# PIC_WIFI_DEV.net
KiCad netlist of a schematic drawn in EAGLE
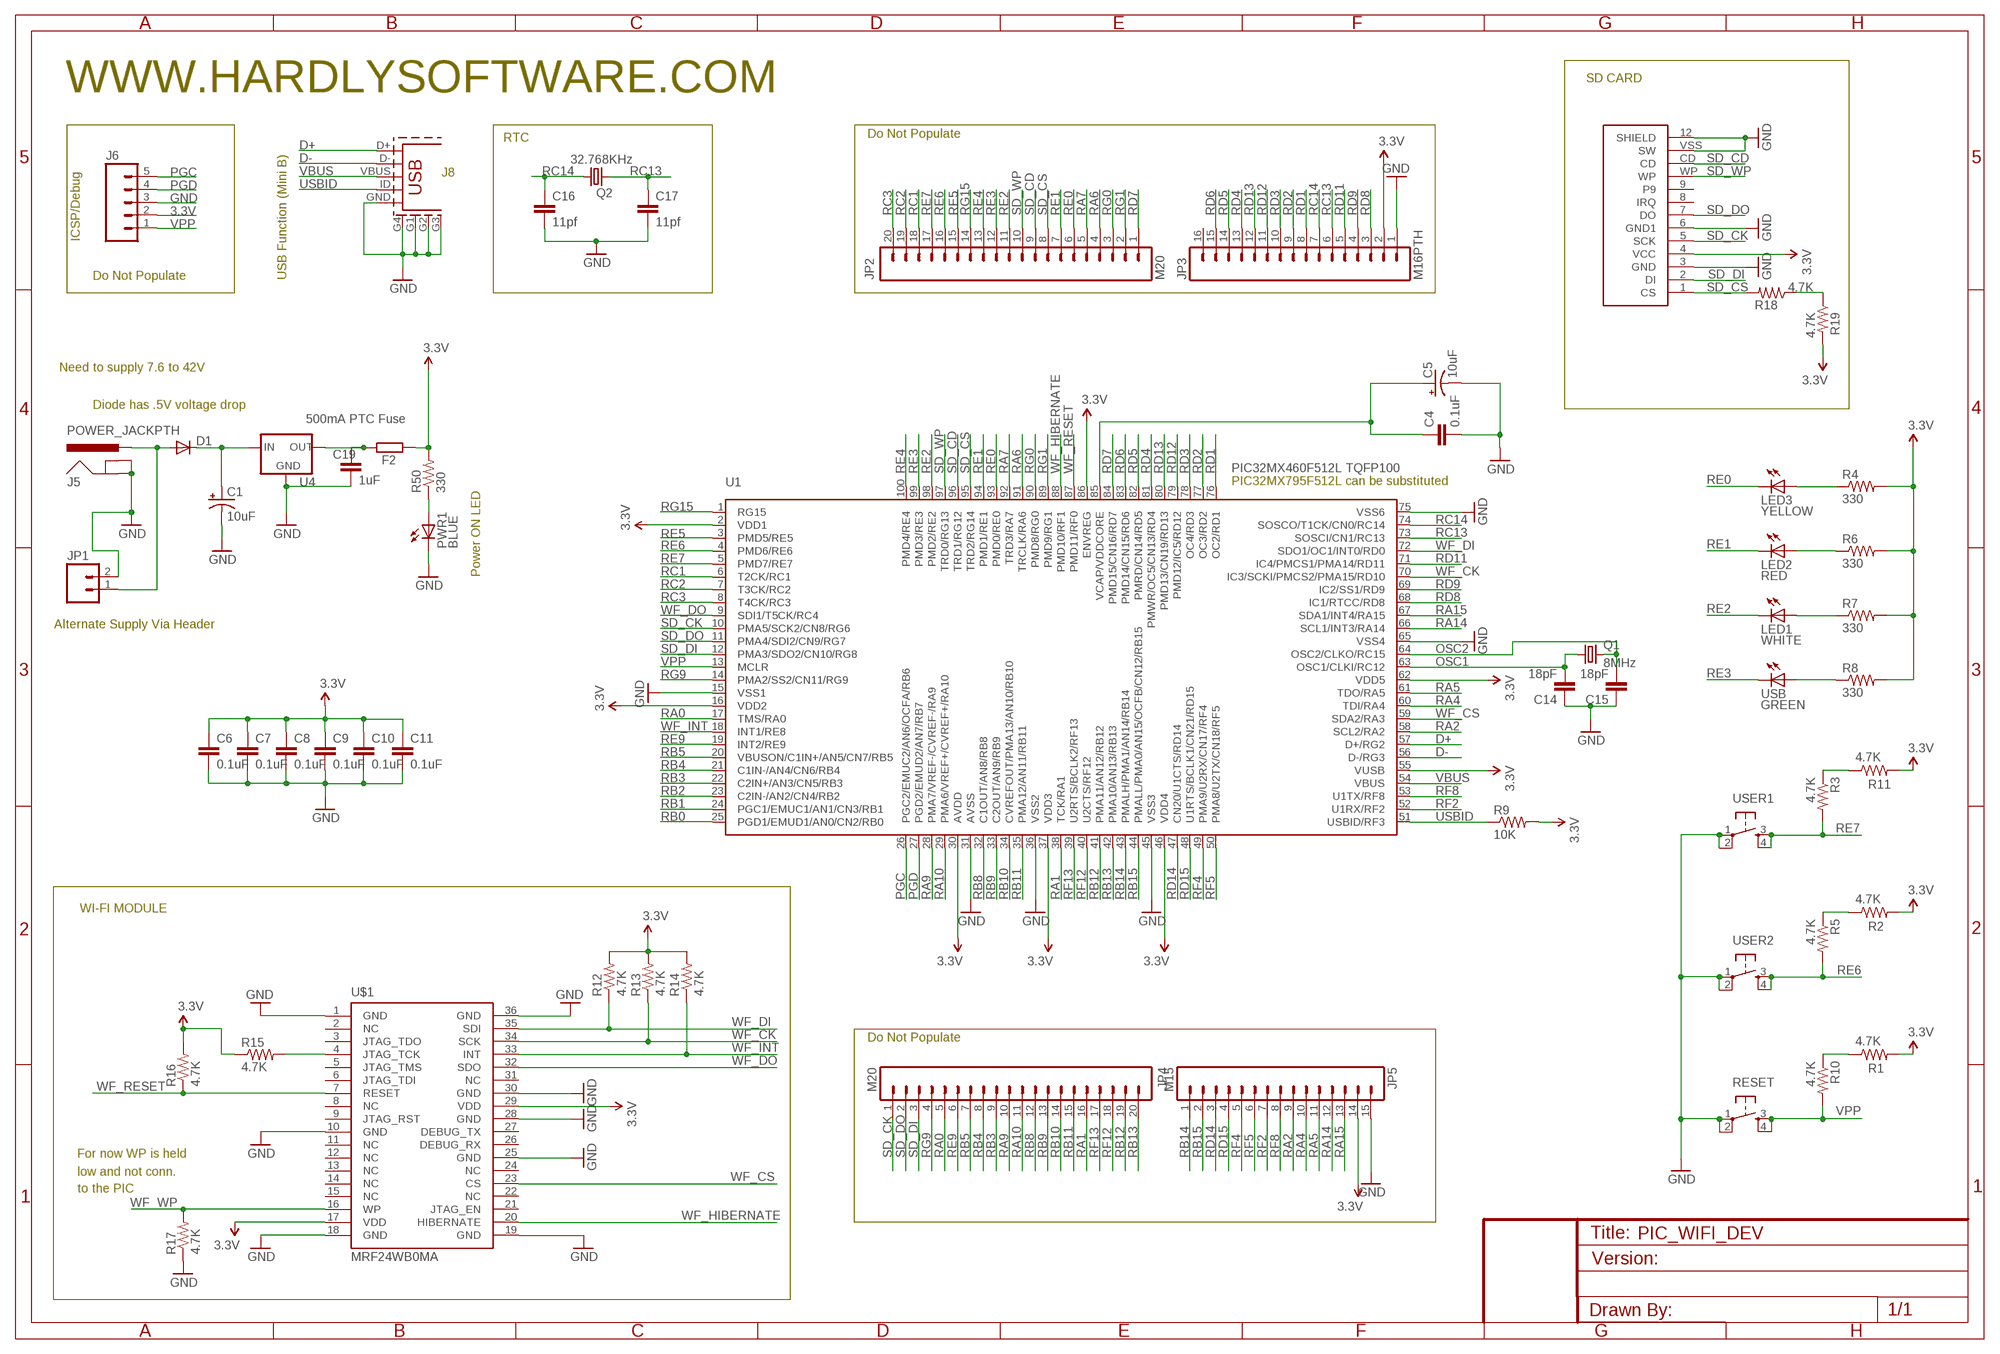
[diagram p0: schematic, sheet 1]

(export (version "E")
  (design (tool "Eeschema 10.0.6"))
  (components
    (comp (ref "C1")
      (value "10uF")
      (footprint "eagle-import:EIA3528")
      (libsource (lib "eagle-import") (part "CAP_POL3528"))
    )
    (comp (ref "C4")
      (value "0.1uF")
      (footprint "eagle-import:C0402")
      (libsource (lib "eagle-import") (part "CAP0402"))
    )
    (comp (ref "C5")
      (value "10uF")
      (footprint "eagle-import:EIA3528")
      (libsource (lib "eagle-import") (part "CAP_POL3528"))
    )
    (comp (ref "C6")
      (value "0.1uF")
      (footprint "eagle-import:C0402")
      (libsource (lib "eagle-import") (part "CAP0402"))
    )
    (comp (ref "C7")
      (value "0.1uF")
      (footprint "eagle-import:C0402")
      (libsource (lib "eagle-import") (part "CAP0402"))
    )
    (comp (ref "C8")
      (value "0.1uF")
      (footprint "eagle-import:C0402")
      (libsource (lib "eagle-import") (part "CAP0402"))
    )
    (comp (ref "C9")
      (value "0.1uF")
      (footprint "eagle-import:C0402")
      (libsource (lib "eagle-import") (part "CAP0402"))
    )
    (comp (ref "C10")
      (value "0.1uF")
      (footprint "eagle-import:C0402")
      (libsource (lib "eagle-import") (part "SparkFun02-20-08_CAP0402"))
    )
    (comp (ref "C11")
      (value "0.1uF")
      (footprint "eagle-import:C0402")
      (libsource (lib "eagle-import") (part "CAP0402"))
    )
    (comp (ref "C14")
      (value "18pF")
      (footprint "eagle-import:C0402")
      (libsource (lib "eagle-import") (part "CAP0402"))
    )
    (comp (ref "C15")
      (value "18pF")
      (footprint "eagle-import:C0402")
      (libsource (lib "eagle-import") (part "CAP0402"))
    )
    (comp (ref "C16")
      (value "11pf")
      (footprint "eagle-import:C0402")
      (libsource (lib "eagle-import") (part "CAP0402"))
    )
    (comp (ref "C17")
      (value "11pf")
      (footprint "eagle-import:C0402")
      (libsource (lib "eagle-import") (part "CAP0402"))
    )
    (comp (ref "C19")
      (value "1uF")
      (footprint "eagle-import:0603-CAP")
      (libsource (lib "eagle-import") (part "CAP0603-CAP"))
    )
    (comp (ref "D1")
      (value "DIODESMA")
      (footprint "eagle-import:SMA-DIODE")
      (libsource (lib "eagle-import") (part "DIODESMA"))
    )
    (comp (ref "F2")
      (value "500mA PTC Fuse")
      (footprint "eagle-import:M1206")
      (libsource (lib "eagle-import") (part "R-EU_M1206"))
    )
    (comp (ref "J5")
      (value "POWER_JACKPTH")
      (footprint "eagle-import:POWER_JACK_PTH")
      (libsource (lib "eagle-import") (part "POWER_JACKPTH"))
    )
    (comp (ref "J6")
      (value "M05PTH")
      (footprint "eagle-import:1X05")
      (libsource (lib "eagle-import") (part "M05PTH"))
    )
    (comp (ref "J8")
      (value "USB_5PIN")
      (footprint "eagle-import:USB-MINIB")
      (libsource (lib "eagle-import") (part "USB_5PIN"))
    )
    (comp (ref "JP1")
      (value "M02PTH")
      (footprint "eagle-import:1X02")
      (libsource (lib "eagle-import") (part "M02PTH"))
    )
    (comp (ref "JP2")
      (value "M20")
      (footprint "eagle-import:1X20")
      (libsource (lib "eagle-import") (part "M20"))
    )
    (comp (ref "JP3")
      (value "M16PTH")
      (footprint "eagle-import:1X16")
      (libsource (lib "eagle-import") (part "M16PTH"))
    )
    (comp (ref "JP4")
      (value "M20")
      (footprint "eagle-import:1X20")
      (libsource (lib "eagle-import") (part "M20"))
    )
    (comp (ref "JP5")
      (value "M15")
      (footprint "eagle-import:1X15")
      (libsource (lib "eagle-import") (part "M15"))
    )
    (comp (ref "LED1")
      (value "WHITE")
      (footprint "eagle-import:LED-0603")
      (libsource (lib "eagle-import") (part "LED0603"))
    )
    (comp (ref "LED2")
      (value "RED")
      (footprint "eagle-import:LED-0603")
      (libsource (lib "eagle-import") (part "LED0603"))
    )
    (comp (ref "LED3")
      (value "YELLOW")
      (footprint "eagle-import:LED-0603")
      (libsource (lib "eagle-import") (part "LED0603"))
    )
    (comp (ref "PWR1")
      (value "BLUE")
      (footprint "eagle-import:LED-0603")
      (libsource (lib "eagle-import") (part "LED0603"))
    )
    (comp (ref "Q1")
      (value "8MHz")
      (footprint "eagle-import:CRYSTAL-SMD-5X3")
      (libsource (lib "eagle-import") (part "CRYSTAL5X3"))
    )
    (comp (ref "Q2")
      (value "32.768KHz")
      (footprint "eagle-import:CRYSTAL-SMD-4X2")
      (libsource (lib "eagle-import") (part "CRYSTAL4X2"))
    )
    (comp (ref "R1")
      (value "4.7K")
      (footprint "eagle-import:C0402")
      (libsource (lib "eagle-import") (part "RESISTOR0402"))
    )
    (comp (ref "R2")
      (value "4.7K")
      (footprint "eagle-import:C0402")
      (libsource (lib "eagle-import") (part "RESISTOR0402"))
    )
    (comp (ref "R3")
      (value "4.7K")
      (footprint "eagle-import:C0402")
      (libsource (lib "eagle-import") (part "RESISTOR0402"))
    )
    (comp (ref "R4")
      (value "330")
      (footprint "eagle-import:C0402")
      (libsource (lib "eagle-import") (part "RESISTOR0402"))
    )
    (comp (ref "R5")
      (value "4.7K")
      (footprint "eagle-import:C0402")
      (libsource (lib "eagle-import") (part "RESISTOR0402"))
    )
    (comp (ref "R6")
      (value "330")
      (footprint "eagle-import:C0402")
      (libsource (lib "eagle-import") (part "RESISTOR0402"))
    )
    (comp (ref "R7")
      (value "330")
      (footprint "eagle-import:C0402")
      (libsource (lib "eagle-import") (part "RESISTOR0402"))
    )
    (comp (ref "R8")
      (value "330")
      (footprint "eagle-import:C0402")
      (libsource (lib "eagle-import") (part "RESISTOR0402"))
    )
    (comp (ref "R9")
      (value "10K")
      (footprint "eagle-import:C0402")
      (libsource (lib "eagle-import") (part "RESISTOR0402"))
    )
    (comp (ref "R10")
      (value "4.7K")
      (footprint "eagle-import:C0402")
      (libsource (lib "eagle-import") (part "RESISTOR0402"))
    )
    (comp (ref "R11")
      (value "4.7K")
      (footprint "eagle-import:C0402")
      (libsource (lib "eagle-import") (part "RESISTOR0402"))
    )
    (comp (ref "R12")
      (value "4.7K")
      (footprint "eagle-import:0603-RES")
      (libsource (lib "eagle-import") (part "RESISTOR0603-RES"))
    )
    (comp (ref "R13")
      (value "4.7K")
      (footprint "eagle-import:0603-RES")
      (libsource (lib "eagle-import") (part "RESISTOR0603-RES"))
    )
    (comp (ref "R14")
      (value "4.7K")
      (footprint "eagle-import:0603-RES")
      (libsource (lib "eagle-import") (part "RESISTOR0603-RES"))
    )
    (comp (ref "R15")
      (value "4.7K")
      (footprint "eagle-import:0603-RES")
      (libsource (lib "eagle-import") (part "RESISTOR0603-RES"))
    )
    (comp (ref "R16")
      (value "4.7K")
      (footprint "eagle-import:0603-RES")
      (libsource (lib "eagle-import") (part "RESISTOR0603-RES"))
    )
    (comp (ref "R17")
      (value "4.7K")
      (footprint "eagle-import:0603-RES")
      (libsource (lib "eagle-import") (part "RESISTOR0603-RES"))
    )
    (comp (ref "R18")
      (value "4.7K")
      (footprint "eagle-import:0603-RES")
      (libsource (lib "eagle-import") (part "RESISTOR0603-RES"))
    )
    (comp (ref "R19")
      (value "4.7K")
      (footprint "eagle-import:0603-RES")
      (libsource (lib "eagle-import") (part "RESISTOR0603-RES"))
    )
    (comp (ref "R50")
      (value "330")
      (footprint "eagle-import:0603-RES")
      (libsource (lib "eagle-import") (part "RESISTOR0603-RES"))
    )
    (comp (ref "RESET")
      (value "TAC_SWITCHB3FS")
      (footprint "eagle-import:SWITCH-OMRON")
      (libsource (lib "eagle-import") (part "TAC_SWITCHB3FS"))
    )
    (comp (ref "U$1")
      (value "MRF24WB0MA")
      (footprint "eagle-import:SMD_MRF")
      (libsource (lib "eagle-import") (part "MRF24WB0MA"))
    )
    (comp (ref "U$2")
      (value "SD_CARD_SOCKETALPS")
      (footprint "eagle-import:SD_ALPS")
      (libsource (lib "eagle-import") (part "SD_CARD_SOCKETALPS"))
    )
    (comp (ref "U1")
      (value "PIC32MX460F512L TQFP100")
      (footprint "eagle-import:TQFP100")
      (libsource (lib "eagle-import") (part "PIC32MX4XXLTQFP100"))
    )
    (comp (ref "U4")
      (value "RECOM_X.X_REG78XX")
      (footprint "eagle-import:RECOM")
      (libsource (lib "eagle-import") (part "RECOM_X.X_REG78XX"))
    )
    (comp (ref "USB")
      (value "GREEN")
      (footprint "eagle-import:LED-0603")
      (libsource (lib "eagle-import") (part "LED0603"))
    )
    (comp (ref "USER1")
      (value "TAC_SWITCHB3FS")
      (footprint "eagle-import:SWITCH-OMRON")
      (libsource (lib "eagle-import") (part "TAC_SWITCHB3FS"))
    )
    (comp (ref "USER2")
      (value "TAC_SWITCHB3FS")
      (footprint "eagle-import:SWITCH-OMRON")
      (libsource (lib "eagle-import") (part "TAC_SWITCHB3FS"))
    )
  )
  (nets
    (net (code "1") (name "/D+") (class "Default")
      (node (ref "J8") (pin "D+") (pinfunction "D+_D+") (pintype "bidirectional"))
      (node (ref "U1") (pin "57") (pinfunction "D+/RG2_57") (pintype "bidirectional"))
    )
    (net (code "2") (name "/D-") (class "Default")
      (node (ref "J8") (pin "D-") (pinfunction "D-_D-") (pintype "bidirectional"))
      (node (ref "U1") (pin "56") (pinfunction "D-/RG3_56") (pintype "bidirectional"))
    )
    (net (code "3") (name "/OSC1") (class "Default")
      (node (ref "C14") (pin "2") (pinfunction "2_2") (pintype "passive"))
      (node (ref "Q1") (pin "1") (pinfunction "1_1") (pintype "passive"))
      (node (ref "U1") (pin "63") (pinfunction "OSC1/CLKI/RC12_63") (pintype "bidirectional"))
    )
    (net (code "4") (name "/OSC2") (class "Default")
      (node (ref "C15") (pin "2") (pinfunction "2_2") (pintype "passive"))
      (node (ref "Q1") (pin "3") (pinfunction "2_3") (pintype "passive"))
      (node (ref "U1") (pin "64") (pinfunction "OSC2/CLKO/RC15_64") (pintype "bidirectional"))
    )
    (net (code "5") (name "/PGC") (class "Default")
      (node (ref "J6") (pin "5") (pinfunction "5_5") (pintype "passive"))
      (node (ref "U1") (pin "26") (pinfunction "PGC2/EMUC2/AN6/OCFA/RB6_26") (pintype "bidirectional"))
    )
    (net (code "6") (name "/PGD") (class "Default")
      (node (ref "J6") (pin "4") (pinfunction "4_4") (pintype "passive"))
      (node (ref "U1") (pin "27") (pinfunction "PGD2/EMUD2/AN7/RB7_27") (pintype "bidirectional"))
    )
    (net (code "7") (name "/RA0") (class "Default")
      (node (ref "JP4") (pin "5") (pinfunction "5_5") (pintype "passive"))
      (node (ref "U1") (pin "17") (pinfunction "TMS/RA0_17") (pintype "bidirectional"))
    )
    (net (code "8") (name "/RA1") (class "Default")
      (node (ref "JP4") (pin "16") (pinfunction "16_16") (pintype "passive"))
      (node (ref "U1") (pin "38") (pinfunction "TCK/RA1_38") (pintype "bidirectional"))
    )
    (net (code "9") (name "/RA2") (class "Default")
      (node (ref "JP5") (pin "9") (pinfunction "9_9") (pintype "passive"))
      (node (ref "U1") (pin "58") (pinfunction "SCL2/RA2_58") (pintype "bidirectional"))
    )
    (net (code "10") (name "/RA4") (class "Default")
      (node (ref "JP5") (pin "10") (pinfunction "10_10") (pintype "passive"))
      (node (ref "U1") (pin "60") (pinfunction "TDI/RA4_60") (pintype "bidirectional"))
    )
    (net (code "11") (name "/RA5") (class "Default")
      (node (ref "JP5") (pin "11") (pinfunction "11_11") (pintype "passive"))
      (node (ref "U1") (pin "61") (pinfunction "TDO/RA5_61") (pintype "bidirectional"))
    )
    (net (code "12") (name "/RA6") (class "Default")
      (node (ref "JP2") (pin "4") (pinfunction "4_4") (pintype "passive"))
      (node (ref "U1") (pin "91") (pinfunction "TRCLK/RA6_91") (pintype "bidirectional"))
    )
    (net (code "13") (name "/RA7") (class "Default")
      (node (ref "JP2") (pin "5") (pinfunction "5_5") (pintype "passive"))
      (node (ref "U1") (pin "92") (pinfunction "TRD3/RA7_92") (pintype "bidirectional"))
    )
    (net (code "14") (name "/RA9") (class "Default")
      (node (ref "JP4") (pin "10") (pinfunction "10_10") (pintype "passive"))
      (node (ref "U1") (pin "28") (pinfunction "PMA7/VREF-/CVREF-/RA9_28") (pintype "bidirectional"))
    )
    (net (code "15") (name "/RA10") (class "Default")
      (node (ref "JP4") (pin "11") (pinfunction "11_11") (pintype "passive"))
      (node (ref "U1") (pin "29") (pinfunction "PMA6/VREF+/CVREF+/RA10_29") (pintype "bidirectional"))
    )
    (net (code "16") (name "/RA14") (class "Default")
      (node (ref "JP5") (pin "12") (pinfunction "12_12") (pintype "passive"))
      (node (ref "U1") (pin "66") (pinfunction "SCL1/INT3/RA14_66") (pintype "bidirectional"))
    )
    (net (code "17") (name "/RA15") (class "Default")
      (node (ref "JP5") (pin "13") (pinfunction "13_13") (pintype "passive"))
      (node (ref "U1") (pin "67") (pinfunction "SDA1/INT4/RA15_67") (pintype "bidirectional"))
    )
    (net (code "18") (name "/RB0") (class "Default")
      (node (ref "U1") (pin "25") (pinfunction "PGD1/EMUD1/AN0/CN2/RB0_25") (pintype "bidirectional"))
    )
    (net (code "19") (name "/RB1") (class "Default")
      (node (ref "U1") (pin "24") (pinfunction "PGC1/EMUC1/AN1/CN3/RB1_24") (pintype "bidirectional"))
    )
    (net (code "20") (name "/RB2") (class "Default")
      (node (ref "U1") (pin "23") (pinfunction "C2IN-/AN2/CN4/RB2_23") (pintype "bidirectional"))
    )
    (net (code "21") (name "/RB3") (class "Default")
      (node (ref "JP4") (pin "9") (pinfunction "9_9") (pintype "passive"))
      (node (ref "U1") (pin "22") (pinfunction "C2IN+/AN3/CN5/RB3_22") (pintype "bidirectional"))
    )
    (net (code "22") (name "/RB4") (class "Default")
      (node (ref "JP4") (pin "8") (pinfunction "8_8") (pintype "passive"))
      (node (ref "U1") (pin "21") (pinfunction "C1IN-/AN4/CN6/RB4_21") (pintype "bidirectional"))
    )
    (net (code "23") (name "/RB5") (class "Default")
      (node (ref "JP4") (pin "7") (pinfunction "7_7") (pintype "passive"))
      (node (ref "U1") (pin "20") (pinfunction "VBUSON/C1IN+/AN5/CN7/RB5_20") (pintype "bidirectional"))
    )
    (net (code "24") (name "/RB8") (class "Default")
      (node (ref "JP4") (pin "12") (pinfunction "12_12") (pintype "passive"))
      (node (ref "U1") (pin "32") (pinfunction "C1OUT/AN8/RB8_32") (pintype "bidirectional"))
    )
    (net (code "25") (name "/RB9") (class "Default")
      (node (ref "JP4") (pin "13") (pinfunction "13_13") (pintype "passive"))
      (node (ref "U1") (pin "33") (pinfunction "C2OUT/AN9/RB9_33") (pintype "bidirectional"))
    )
    (net (code "26") (name "/RB10") (class "Default")
      (node (ref "JP4") (pin "14") (pinfunction "14_14") (pintype "passive"))
      (node (ref "U1") (pin "34") (pinfunction "CVREFOUT/PMA13/AN10/RB10_34") (pintype "bidirectional"))
    )
    (net (code "27") (name "/RB11") (class "Default")
      (node (ref "JP4") (pin "15") (pinfunction "15_15") (pintype "passive"))
      (node (ref "U1") (pin "35") (pinfunction "PMA12/AN11/RB11_35") (pintype "bidirectional"))
    )
    (net (code "28") (name "/RB12") (class "Default")
      (node (ref "JP4") (pin "19") (pinfunction "19_19") (pintype "passive"))
      (node (ref "U1") (pin "41") (pinfunction "PMA11/AN12/RB12_41") (pintype "bidirectional"))
    )
    (net (code "29") (name "/RB13") (class "Default")
      (node (ref "JP4") (pin "20") (pinfunction "20_20") (pintype "passive"))
      (node (ref "U1") (pin "42") (pinfunction "PMA10/AN13/RB13_42") (pintype "bidirectional"))
    )
    (net (code "30") (name "/RB14") (class "Default")
      (node (ref "JP5") (pin "1") (pinfunction "1_1") (pintype "passive"))
      (node (ref "U1") (pin "43") (pinfunction "PMALH/PMA1/AN14/RB14_43") (pintype "bidirectional"))
    )
    (net (code "31") (name "/RB15") (class "Default")
      (node (ref "JP5") (pin "2") (pinfunction "2_2") (pintype "passive"))
      (node (ref "U1") (pin "44") (pinfunction "PMALL/PMA0/AN15/OCFB/CN12/RB15_44") (pintype "bidirectional"))
    )
    (net (code "32") (name "/RC1") (class "Default")
      (node (ref "JP2") (pin "18") (pinfunction "18_18") (pintype "passive"))
      (node (ref "U1") (pin "6") (pinfunction "T2CK/RC1_6") (pintype "bidirectional"))
    )
    (net (code "33") (name "/RC2") (class "Default")
      (node (ref "JP2") (pin "19") (pinfunction "19_19") (pintype "passive"))
      (node (ref "U1") (pin "7") (pinfunction "T3CK/RC2_7") (pintype "bidirectional"))
    )
    (net (code "34") (name "/RC3") (class "Default")
      (node (ref "JP2") (pin "20") (pinfunction "20_20") (pintype "passive"))
      (node (ref "U1") (pin "8") (pinfunction "T4CK/RC3_8") (pintype "bidirectional"))
    )
    (net (code "35") (name "/RC13") (class "Default")
      (node (ref "C17") (pin "1") (pinfunction "1_1") (pintype "passive"))
      (node (ref "JP3") (pin "6") (pinfunction "6_6") (pintype "passive"))
      (node (ref "Q2") (pin "P$2") (pinfunction "2_P$2") (pintype "passive"))
      (node (ref "U1") (pin "73") (pinfunction "SOSCI/CN1/RC13_73") (pintype "bidirectional"))
    )
    (net (code "36") (name "/RC14") (class "Default")
      (node (ref "C16") (pin "1") (pinfunction "1_1") (pintype "passive"))
      (node (ref "JP3") (pin "7") (pinfunction "7_7") (pintype "passive"))
      (node (ref "Q2") (pin "P$1") (pinfunction "1_P$1") (pintype "passive"))
      (node (ref "U1") (pin "74") (pinfunction "SOSCO/T1CK/CN0/RC14_74") (pintype "bidirectional"))
    )
    (net (code "37") (name "/RD1") (class "Default")
      (node (ref "JP3") (pin "8") (pinfunction "8_8") (pintype "passive"))
      (node (ref "U1") (pin "76") (pinfunction "OC2/RD1_76") (pintype "bidirectional"))
    )
    (net (code "38") (name "/RD2") (class "Default")
      (node (ref "JP3") (pin "9") (pinfunction "9_9") (pintype "passive"))
      (node (ref "U1") (pin "77") (pinfunction "OC3/RD2_77") (pintype "bidirectional"))
    )
    (net (code "39") (name "/RD3") (class "Default")
      (node (ref "JP3") (pin "10") (pinfunction "10_10") (pintype "passive"))
      (node (ref "U1") (pin "78") (pinfunction "OC4/RD3_78") (pintype "bidirectional"))
    )
    (net (code "40") (name "/RD4") (class "Default")
      (node (ref "JP3") (pin "13") (pinfunction "13_13") (pintype "passive"))
      (node (ref "U1") (pin "81") (pinfunction "PMWR/OC5/CN13/RD4_81") (pintype "bidirectional"))
    )
    (net (code "41") (name "/RD5") (class "Default")
      (node (ref "JP3") (pin "14") (pinfunction "14_14") (pintype "passive"))
      (node (ref "U1") (pin "82") (pinfunction "PMRD/CN14/RD5_82") (pintype "bidirectional"))
    )
    (net (code "42") (name "/RD6") (class "Default")
      (node (ref "JP3") (pin "15") (pinfunction "15_15") (pintype "passive"))
      (node (ref "U1") (pin "83") (pinfunction "PMD14/CN15/RD6_83") (pintype "bidirectional"))
    )
    (net (code "43") (name "/RD7") (class "Default")
      (node (ref "JP2") (pin "1") (pinfunction "1_1") (pintype "passive"))
      (node (ref "U1") (pin "84") (pinfunction "PMD15/CN16/RD7_84") (pintype "bidirectional"))
    )
    (net (code "44") (name "/RD8") (class "Default")
      (node (ref "JP3") (pin "3") (pinfunction "3_3") (pintype "passive"))
      (node (ref "U1") (pin "68") (pinfunction "IC1/RTCC/RD8_68") (pintype "bidirectional"))
    )
    (net (code "45") (name "/RD9") (class "Default")
      (node (ref "JP3") (pin "4") (pinfunction "4_4") (pintype "passive"))
      (node (ref "U1") (pin "69") (pinfunction "IC2/SS1/RD9_69") (pintype "bidirectional"))
    )
    (net (code "46") (name "/RD11") (class "Default")
      (node (ref "JP3") (pin "5") (pinfunction "5_5") (pintype "passive"))
      (node (ref "U1") (pin "71") (pinfunction "IC4/PMCS1/PMA14/RD11_71") (pintype "bidirectional"))
    )
    (net (code "47") (name "/RD12") (class "Default")
      (node (ref "JP3") (pin "11") (pinfunction "11_11") (pintype "passive"))
      (node (ref "U1") (pin "79") (pinfunction "PMD12/IC5/RD12_79") (pintype "bidirectional"))
    )
    (net (code "48") (name "/RD13") (class "Default")
      (node (ref "JP3") (pin "12") (pinfunction "12_12") (pintype "passive"))
      (node (ref "U1") (pin "80") (pinfunction "PMD13/CN19/RD13_80") (pintype "bidirectional"))
    )
    (net (code "49") (name "/RD14") (class "Default")
      (node (ref "JP5") (pin "3") (pinfunction "3_3") (pintype "passive"))
      (node (ref "U1") (pin "47") (pinfunction "CN20/U1CTS/RD14_47") (pintype "bidirectional"))
    )
    (net (code "50") (name "/RD15") (class "Default")
      (node (ref "JP5") (pin "4") (pinfunction "4_4") (pintype "passive"))
      (node (ref "U1") (pin "48") (pinfunction "U1RTS/BCLK1/CN21/RD15_48") (pintype "bidirectional"))
    )
    (net (code "51") (name "/RE0") (class "Default")
      (node (ref "JP2") (pin "6") (pinfunction "6_6") (pintype "passive"))
      (node (ref "LED3") (pin "C") (pinfunction "C_C") (pintype "passive"))
      (node (ref "U1") (pin "93") (pinfunction "PMD0/RE0_93") (pintype "bidirectional"))
    )
    (net (code "52") (name "/RE1") (class "Default")
      (node (ref "JP2") (pin "7") (pinfunction "7_7") (pintype "passive"))
      (node (ref "LED2") (pin "C") (pinfunction "C_C") (pintype "passive"))
      (node (ref "U1") (pin "94") (pinfunction "PMD1/RE1_94") (pintype "bidirectional"))
    )
    (net (code "53") (name "/RE2") (class "Default")
      (node (ref "JP2") (pin "11") (pinfunction "11_11") (pintype "passive"))
      (node (ref "LED1") (pin "C") (pinfunction "C_C") (pintype "passive"))
      (node (ref "U1") (pin "98") (pinfunction "PMD2/RE2_98") (pintype "bidirectional"))
    )
    (net (code "54") (name "/RE3") (class "Default")
      (node (ref "JP2") (pin "12") (pinfunction "12_12") (pintype "passive"))
      (node (ref "U1") (pin "99") (pinfunction "PMD3/RE3_99") (pintype "bidirectional"))
      (node (ref "USB") (pin "C") (pinfunction "C_C") (pintype "passive"))
    )
    (net (code "55") (name "/RE4") (class "Default")
      (node (ref "JP2") (pin "13") (pinfunction "13_13") (pintype "passive"))
      (node (ref "U1") (pin "100") (pinfunction "PMD4/RE4_100") (pintype "bidirectional"))
    )
    (net (code "56") (name "/RE5") (class "Default")
      (node (ref "JP2") (pin "15") (pinfunction "15_15") (pintype "passive"))
      (node (ref "U1") (pin "3") (pinfunction "PMD5/RE5_3") (pintype "bidirectional"))
    )
    (net (code "57") (name "/RE6") (class "Default")
      (node (ref "JP2") (pin "16") (pinfunction "16_16") (pintype "passive"))
      (node (ref "R5") (pin "2") (pinfunction "2_2") (pintype "passive"))
      (node (ref "U1") (pin "4") (pinfunction "PMD6/RE6_4") (pintype "bidirectional"))
      (node (ref "USER2") (pin "3") (pinfunction "3_3") (pintype "passive"))
      (node (ref "USER2") (pin "4") (pinfunction "4_4") (pintype "passive"))
    )
    (net (code "58") (name "/RE7") (class "Default")
      (node (ref "JP2") (pin "17") (pinfunction "17_17") (pintype "passive"))
      (node (ref "R3") (pin "2") (pinfunction "2_2") (pintype "passive"))
      (node (ref "U1") (pin "5") (pinfunction "PMD7/RE7_5") (pintype "bidirectional"))
      (node (ref "USER1") (pin "3") (pinfunction "3_3") (pintype "passive"))
      (node (ref "USER1") (pin "4") (pinfunction "4_4") (pintype "passive"))
    )
    (net (code "59") (name "/RE9") (class "Default")
      (node (ref "JP4") (pin "6") (pinfunction "6_6") (pintype "passive"))
      (node (ref "U1") (pin "19") (pinfunction "INT2/RE9_19") (pintype "bidirectional"))
    )
    (net (code "60") (name "/RF2") (class "Default")
      (node (ref "JP5") (pin "7") (pinfunction "7_7") (pintype "passive"))
      (node (ref "U1") (pin "52") (pinfunction "U1RX/RF2_52") (pintype "bidirectional"))
    )
    (net (code "61") (name "/RF4") (class "Default")
      (node (ref "JP5") (pin "5") (pinfunction "5_5") (pintype "passive"))
      (node (ref "U1") (pin "49") (pinfunction "PMA9/U2RX/CN17/RF4_49") (pintype "bidirectional"))
    )
    (net (code "62") (name "/RF5") (class "Default")
      (node (ref "JP5") (pin "6") (pinfunction "6_6") (pintype "passive"))
      (node (ref "U1") (pin "50") (pinfunction "PMA8/U2TX/CN18/RF5_50") (pintype "bidirectional"))
    )
    (net (code "63") (name "/RF8") (class "Default")
      (node (ref "JP5") (pin "8") (pinfunction "8_8") (pintype "passive"))
      (node (ref "U1") (pin "53") (pinfunction "U1TX/RF8_53") (pintype "bidirectional"))
    )
    (net (code "64") (name "/RF12") (class "Default")
      (node (ref "JP4") (pin "18") (pinfunction "18_18") (pintype "passive"))
      (node (ref "U1") (pin "40") (pinfunction "U2CTS/RF12_40") (pintype "bidirectional"))
    )
    (net (code "65") (name "/RF13") (class "Default")
      (node (ref "JP4") (pin "17") (pinfunction "17_17") (pintype "passive"))
      (node (ref "U1") (pin "39") (pinfunction "U2RTS/BCLK2/RF13_39") (pintype "bidirectional"))
    )
    (net (code "66") (name "/RG0") (class "Default")
      (node (ref "JP2") (pin "3") (pinfunction "3_3") (pintype "passive"))
      (node (ref "U1") (pin "90") (pinfunction "PMD8/RG0_90") (pintype "bidirectional"))
    )
    (net (code "67") (name "/RG1") (class "Default")
      (node (ref "JP2") (pin "2") (pinfunction "2_2") (pintype "passive"))
      (node (ref "U1") (pin "89") (pinfunction "PMD9/RG1_89") (pintype "bidirectional"))
    )
    (net (code "68") (name "/RG9") (class "Default")
      (node (ref "JP4") (pin "4") (pinfunction "4_4") (pintype "passive"))
      (node (ref "U1") (pin "14") (pinfunction "PMA2/SS2/CN11/RG9_14") (pintype "bidirectional"))
    )
    (net (code "69") (name "/RG15") (class "Default")
      (node (ref "JP2") (pin "14") (pinfunction "14_14") (pintype "passive"))
      (node (ref "U1") (pin "1") (pinfunction "RG15_1") (pintype "bidirectional"))
    )
    (net (code "70") (name "/SD_CD") (class "Default")
      (node (ref "JP2") (pin "9") (pinfunction "9_9") (pintype "passive"))
      (node (ref "U$2") (pin "CD") (pinfunction "CD_CD") (pintype "bidirectional"))
      (node (ref "U1") (pin "96") (pinfunction "TRD1/RG12_96") (pintype "bidirectional"))
    )
    (net (code "71") (name "/SD_CK") (class "Default")
      (node (ref "JP4") (pin "1") (pinfunction "1_1") (pintype "passive"))
      (node (ref "U$2") (pin "5") (pinfunction "SCK_5") (pintype "bidirectional"))
      (node (ref "U1") (pin "10") (pinfunction "PMA5/SCK2/CN8/RG6_10") (pintype "bidirectional"))
    )
    (net (code "72") (name "/SD_CS") (class "Default")
      (node (ref "JP2") (pin "8") (pinfunction "8_8") (pintype "passive"))
      (node (ref "R18") (pin "2") (pinfunction "2_2") (pintype "passive"))
      (node (ref "U$2") (pin "1") (pinfunction "CS_1") (pintype "bidirectional"))
      (node (ref "U1") (pin "95") (pinfunction "TRD2/RG14_95") (pintype "bidirectional"))
    )
    (net (code "73") (name "/SD_DI") (class "Default")
      (node (ref "JP4") (pin "3") (pinfunction "3_3") (pintype "passive"))
      (node (ref "U$2") (pin "2") (pinfunction "DI_2") (pintype "bidirectional"))
      (node (ref "U1") (pin "12") (pinfunction "PMA3/SDO2/CN10/RG8_12") (pintype "bidirectional"))
    )
    (net (code "74") (name "/SD_DO") (class "Default")
      (node (ref "JP4") (pin "2") (pinfunction "2_2") (pintype "passive"))
      (node (ref "U$2") (pin "7") (pinfunction "DO_7") (pintype "bidirectional"))
      (node (ref "U1") (pin "11") (pinfunction "PMA4/SDI2/CN9/RG7_11") (pintype "bidirectional"))
    )
    (net (code "75") (name "/SD_WP") (class "Default")
      (node (ref "JP2") (pin "10") (pinfunction "10_10") (pintype "passive"))
      (node (ref "U$2") (pin "WP") (pinfunction "WP_WP") (pintype "bidirectional"))
      (node (ref "U1") (pin "97") (pinfunction "TRD0/RG13_97") (pintype "bidirectional"))
    )
    (net (code "76") (name "/USBID") (class "Default")
      (node (ref "J8") (pin "ID") (pinfunction "USB_ID_ID") (pintype "bidirectional"))
      (node (ref "R9") (pin "1") (pinfunction "1_1") (pintype "passive"))
      (node (ref "U1") (pin "51") (pinfunction "USBID/RF3_51") (pintype "bidirectional"))
    )
    (net (code "77") (name "/VBUS") (class "Default")
      (node (ref "J8") (pin "VBUS") (pinfunction "VBUS_VBUS") (pintype "bidirectional"))
      (node (ref "U1") (pin "54") (pinfunction "VBUS_54") (pintype "bidirectional"))
    )
    (net (code "78") (name "/VPP") (class "Default")
      (node (ref "J6") (pin "1") (pinfunction "1_1") (pintype "passive"))
      (node (ref "R10") (pin "2") (pinfunction "2_2") (pintype "passive"))
      (node (ref "RESET") (pin "3") (pinfunction "3_3") (pintype "passive"))
      (node (ref "RESET") (pin "4") (pinfunction "4_4") (pintype "passive"))
      (node (ref "U1") (pin "13") (pinfunction "MCLR_13") (pintype "bidirectional"))
    )
    (net (code "79") (name "/WF_CK") (class "Default")
      (node (ref "R13") (pin "1") (pinfunction "1_1") (pintype "passive"))
      (node (ref "U$1") (pin "34") (pinfunction "SCK_34") (pintype "bidirectional"))
      (node (ref "U1") (pin "70") (pinfunction "IC3/SCKI/PMCS2/PMA15/RD10_70") (pintype "bidirectional"))
    )
    (net (code "80") (name "/WF_CS") (class "Default")
      (node (ref "U$1") (pin "23") (pinfunction "CS_23") (pintype "bidirectional"))
      (node (ref "U1") (pin "59") (pinfunction "SDA2/RA3_59") (pintype "bidirectional"))
    )
    (net (code "81") (name "/WF_DI") (class "Default")
      (node (ref "R12") (pin "1") (pinfunction "1_1") (pintype "passive"))
      (node (ref "U$1") (pin "35") (pinfunction "SDI_35") (pintype "bidirectional"))
      (node (ref "U1") (pin "72") (pinfunction "SDO1/OC1/INT0/RD0_72") (pintype "bidirectional"))
    )
    (net (code "82") (name "/WF_DO") (class "Default")
      (node (ref "U$1") (pin "32") (pinfunction "SDO_32") (pintype "bidirectional"))
      (node (ref "U1") (pin "9") (pinfunction "SDI1/T5CK/RC4_9") (pintype "bidirectional"))
    )
    (net (code "83") (name "/WF_HIBERNATE") (class "Default")
      (node (ref "U$1") (pin "20") (pinfunction "HIBERNATE_20") (pintype "bidirectional"))
      (node (ref "U1") (pin "88") (pinfunction "PMD10/RF1_88") (pintype "bidirectional"))
    )
    (net (code "84") (name "/WF_INT") (class "Default")
      (node (ref "R14") (pin "1") (pinfunction "1_1") (pintype "passive"))
      (node (ref "U$1") (pin "33") (pinfunction "INT_33") (pintype "bidirectional"))
      (node (ref "U1") (pin "18") (pinfunction "INT1/RE8_18") (pintype "bidirectional"))
    )
    (net (code "85") (name "/WF_RESET") (class "Default")
      (node (ref "R16") (pin "1") (pinfunction "1_1") (pintype "passive"))
      (node (ref "U$1") (pin "7") (pinfunction "RESET_7") (pintype "bidirectional"))
      (node (ref "U1") (pin "87") (pinfunction "PMD11/RF0_87") (pintype "bidirectional"))
    )
    (net (code "86") (name "/WF_WP") (class "Default")
      (node (ref "R17") (pin "2") (pinfunction "2_2") (pintype "passive"))
      (node (ref "U$1") (pin "16") (pinfunction "WP_16") (pintype "bidirectional"))
    )
    (net (code "87") (name "3.3V") (class "Default")
      (node (ref "C10") (pin "1") (pinfunction "1_1") (pintype "passive"))
      (node (ref "C11") (pin "1") (pinfunction "1_1") (pintype "passive"))
      (node (ref "C6") (pin "1") (pinfunction "1_1") (pintype "passive"))
      (node (ref "C7") (pin "1") (pinfunction "1_1") (pintype "passive"))
      (node (ref "C8") (pin "1") (pinfunction "1_1") (pintype "passive"))
      (node (ref "C9") (pin "1") (pinfunction "1_1") (pintype "passive"))
      (node (ref "F2") (pin "1") (pinfunction "1_1") (pintype "passive"))
      (node (ref "J6") (pin "2") (pinfunction "2_2") (pintype "passive"))
      (node (ref "JP3") (pin "2") (pinfunction "2_2") (pintype "passive"))
      (node (ref "JP5") (pin "14") (pinfunction "14_14") (pintype "passive"))
      (node (ref "R1") (pin "2") (pinfunction "2_2") (pintype "passive"))
      (node (ref "R11") (pin "2") (pinfunction "2_2") (pintype "passive"))
      (node (ref "R12") (pin "2") (pinfunction "2_2") (pintype "passive"))
      (node (ref "R13") (pin "2") (pinfunction "2_2") (pintype "passive"))
      (node (ref "R14") (pin "2") (pinfunction "2_2") (pintype "passive"))
      (node (ref "R15") (pin "1") (pinfunction "1_1") (pintype "passive"))
      (node (ref "R16") (pin "2") (pinfunction "2_2") (pintype "passive"))
      (node (ref "R19") (pin "2") (pinfunction "2_2") (pintype "passive"))
      (node (ref "R2") (pin "2") (pinfunction "2_2") (pintype "passive"))
      (node (ref "R4") (pin "2") (pinfunction "2_2") (pintype "passive"))
      (node (ref "R50") (pin "2") (pinfunction "2_2") (pintype "passive"))
      (node (ref "R6") (pin "2") (pinfunction "2_2") (pintype "passive"))
      (node (ref "R7") (pin "2") (pinfunction "2_2") (pintype "passive"))
      (node (ref "R8") (pin "2") (pinfunction "2_2") (pintype "passive"))
      (node (ref "R9") (pin "2") (pinfunction "2_2") (pintype "passive"))
      (node (ref "U$1") (pin "17") (pinfunction "VDD_17") (pintype "bidirectional"))
      (node (ref "U$1") (pin "29") (pinfunction "VDD_29") (pintype "bidirectional"))
      (node (ref "U$2") (pin "4") (pinfunction "VCC_4") (pintype "bidirectional"))
      (node (ref "U1") (pin "16") (pinfunction "VDD2_16") (pintype "bidirectional"))
      (node (ref "U1") (pin "2") (pinfunction "VDD1_2") (pintype "bidirectional"))
      (node (ref "U1") (pin "30") (pinfunction "AVDD_30") (pintype "bidirectional"))
      (node (ref "U1") (pin "37") (pinfunction "VDD3_37") (pintype "bidirectional"))
      (node (ref "U1") (pin "46") (pinfunction "VDD4_46") (pintype "bidirectional"))
      (node (ref "U1") (pin "55") (pinfunction "VUSB_55") (pintype "bidirectional"))
      (node (ref "U1") (pin "62") (pinfunction "VDD5_62") (pintype "bidirectional"))
      (node (ref "U1") (pin "86") (pinfunction "ENVREG_86") (pintype "bidirectional"))
    )
    (net (code "88") (name "GND") (class "Default")
      (node (ref "C1") (pin "C") (pinfunction "-_C") (pintype "passive"))
      (node (ref "C10") (pin "2") (pinfunction "2_2") (pintype "passive"))
      (node (ref "C11") (pin "2") (pinfunction "2_2") (pintype "passive"))
      (node (ref "C14") (pin "1") (pinfunction "1_1") (pintype "passive"))
      (node (ref "C15") (pin "1") (pinfunction "1_1") (pintype "passive"))
      (node (ref "C16") (pin "2") (pinfunction "2_2") (pintype "passive"))
      (node (ref "C17") (pin "2") (pinfunction "2_2") (pintype "passive"))
      (node (ref "C19") (pin "2") (pinfunction "2_2") (pintype "passive"))
      (node (ref "C4") (pin "2") (pinfunction "2_2") (pintype "passive"))
      (node (ref "C5") (pin "C") (pinfunction "-_C") (pintype "passive"))
      (node (ref "C6") (pin "2") (pinfunction "2_2") (pintype "passive"))
      (node (ref "C7") (pin "2") (pinfunction "2_2") (pintype "passive"))
      (node (ref "C8") (pin "2") (pinfunction "2_2") (pintype "passive"))
      (node (ref "C9") (pin "2") (pinfunction "2_2") (pintype "passive"))
      (node (ref "J5") (pin "GND") (pinfunction "GND_GND") (pintype "bidirectional"))
      (node (ref "J5") (pin "GNDBREAK") (pinfunction "GNDBREAK_GNDBREAK") (pintype "bidirectional"))
      (node (ref "J6") (pin "3") (pinfunction "3_3") (pintype "passive"))
      (node (ref "J8") (pin "G1") (pinfunction "P$1_G1") (pintype "bidirectional"))
      (node (ref "J8") (pin "G2") (pinfunction "P$2_G2") (pintype "bidirectional"))
      (node (ref "J8") (pin "G3") (pinfunction "P$3_G3") (pintype "bidirectional"))
      (node (ref "J8") (pin "G4") (pinfunction "SHIELD_G4") (pintype "bidirectional"))
      (node (ref "J8") (pin "GND") (pinfunction "GND_GND") (pintype "bidirectional"))
      (node (ref "JP1") (pin "2") (pinfunction "2_2") (pintype "passive"))
      (node (ref "JP3") (pin "1") (pinfunction "1_1") (pintype "passive"))
      (node (ref "JP5") (pin "15") (pinfunction "15_15") (pintype "passive"))
      (node (ref "PWR1") (pin "C") (pinfunction "C_C") (pintype "passive"))
      (node (ref "R17") (pin "1") (pinfunction "1_1") (pintype "passive"))
      (node (ref "RESET") (pin "1") (pinfunction "1_1") (pintype "passive"))
      (node (ref "RESET") (pin "2") (pinfunction "2_2") (pintype "passive"))
      (node (ref "U$1") (pin "1") (pinfunction "GND_1") (pintype "bidirectional"))
      (node (ref "U$1") (pin "10") (pinfunction "GND_10") (pintype "bidirectional"))
      (node (ref "U$1") (pin "18") (pinfunction "GND_18") (pintype "bidirectional"))
      (node (ref "U$1") (pin "19") (pinfunction "GND_19") (pintype "bidirectional"))
      (node (ref "U$1") (pin "25") (pinfunction "GND_25") (pintype "bidirectional"))
      (node (ref "U$1") (pin "28") (pinfunction "GND_28") (pintype "bidirectional"))
      (node (ref "U$1") (pin "30") (pinfunction "GND_30") (pintype "bidirectional"))
      (node (ref "U$1") (pin "36") (pinfunction "GND_36") (pintype "bidirectional"))
      (node (ref "U$2") (pin "12") (pinfunction "SHIELD_12") (pintype "bidirectional"))
      (node (ref "U$2") (pin "3") (pinfunction "GND_3") (pintype "bidirectional"))
      (node (ref "U$2") (pin "6") (pinfunction "GND1_6") (pintype "bidirectional"))
      (node (ref "U$2") (pin "VSS") (pinfunction "SW_VSS") (pintype "bidirectional"))
      (node (ref "U1") (pin "15") (pinfunction "VSS1_15") (pintype "bidirectional"))
      (node (ref "U1") (pin "31") (pinfunction "AVSS_31") (pintype "bidirectional"))
      (node (ref "U1") (pin "36") (pinfunction "VSS2_36") (pintype "bidirectional"))
      (node (ref "U1") (pin "45") (pinfunction "VSS3_45") (pintype "bidirectional"))
      (node (ref "U1") (pin "65") (pinfunction "VSS4_65") (pintype "bidirectional"))
      (node (ref "U1") (pin "75") (pinfunction "VSS6_75") (pintype "bidirectional"))
      (node (ref "U4") (pin "GND") (pinfunction "GND_GND") (pintype "input"))
      (node (ref "USER1") (pin "1") (pinfunction "1_1") (pintype "passive"))
      (node (ref "USER1") (pin "2") (pinfunction "2_2") (pintype "passive"))
      (node (ref "USER2") (pin "1") (pinfunction "1_1") (pintype "passive"))
      (node (ref "USER2") (pin "2") (pinfunction "2_2") (pintype "passive"))
    )
    (net (code "89") (name "Net-(C1-+)") (class "Default")
      (node (ref "C1") (pin "A") (pinfunction "+_A") (pintype "passive"))
      (node (ref "D1") (pin "C") (pinfunction "C_C") (pintype "passive"))
      (node (ref "U4") (pin "VIN") (pinfunction "IN_VIN") (pintype "input"))
    )
    (net (code "90") (name "Net-(C5-+)") (class "Default")
      (node (ref "C4") (pin "1") (pinfunction "1_1") (pintype "passive"))
      (node (ref "C5") (pin "A") (pinfunction "+_A") (pintype "passive"))
      (node (ref "U1") (pin "85") (pinfunction "VCAP/VDDCORE_85") (pintype "bidirectional"))
    )
    (net (code "91") (name "Net-(D1-PadA)") (class "Default")
      (node (ref "D1") (pin "A") (pinfunction "A_A") (pintype "passive"))
      (node (ref "J5") (pin "PWR") (pinfunction "PWR_PWR") (pintype "bidirectional"))
      (node (ref "JP1") (pin "1") (pinfunction "1_1") (pintype "passive"))
    )
    (net (code "92") (name "Net-(LED1-PadA)") (class "Default")
      (node (ref "LED1") (pin "A") (pinfunction "A_A") (pintype "passive"))
      (node (ref "R7") (pin "1") (pinfunction "1_1") (pintype "passive"))
    )
    (net (code "93") (name "Net-(LED2-PadA)") (class "Default")
      (node (ref "LED2") (pin "A") (pinfunction "A_A") (pintype "passive"))
      (node (ref "R6") (pin "1") (pinfunction "1_1") (pintype "passive"))
    )
    (net (code "94") (name "Net-(LED3-PadA)") (class "Default")
      (node (ref "LED3") (pin "A") (pinfunction "A_A") (pintype "passive"))
      (node (ref "R4") (pin "1") (pinfunction "1_1") (pintype "passive"))
    )
    (net (code "95") (name "Net-(PWR1-PadA)") (class "Default")
      (node (ref "PWR1") (pin "A") (pinfunction "A_A") (pintype "passive"))
      (node (ref "R50") (pin "1") (pinfunction "1_1") (pintype "passive"))
    )
    (net (code "96") (name "Net-(R1-Pad1)") (class "Default")
      (node (ref "R1") (pin "1") (pinfunction "1_1") (pintype "passive"))
      (node (ref "R10") (pin "1") (pinfunction "1_1") (pintype "passive"))
    )
    (net (code "97") (name "Net-(R2-Pad1)") (class "Default")
      (node (ref "R2") (pin "1") (pinfunction "1_1") (pintype "passive"))
      (node (ref "R5") (pin "1") (pinfunction "1_1") (pintype "passive"))
    )
    (net (code "98") (name "Net-(R8-Pad1)") (class "Default")
      (node (ref "R8") (pin "1") (pinfunction "1_1") (pintype "passive"))
      (node (ref "USB") (pin "A") (pinfunction "A_A") (pintype "passive"))
    )
    (net (code "99") (name "Net-(R11-Pad1)") (class "Default")
      (node (ref "R11") (pin "1") (pinfunction "1_1") (pintype "passive"))
      (node (ref "R3") (pin "1") (pinfunction "1_1") (pintype "passive"))
    )
    (net (code "100") (name "Net-(R18-Pad1)") (class "Default")
      (node (ref "R18") (pin "1") (pinfunction "1_1") (pintype "passive"))
      (node (ref "R19") (pin "1") (pinfunction "1_1") (pintype "passive"))
    )
    (net (code "101") (name "Net-(U$1-JTAG_TCK)") (class "Default")
      (node (ref "R15") (pin "2") (pinfunction "2_2") (pintype "passive"))
      (node (ref "U$1") (pin "4") (pinfunction "JTAG_TCK_4") (pintype "bidirectional"))
    )
    (net (code "102") (name "Net-(U4-OUT)") (class "Default")
      (node (ref "C19") (pin "1") (pinfunction "1_1") (pintype "passive"))
      (node (ref "F2") (pin "2") (pinfunction "2_2") (pintype "passive"))
      (node (ref "U4") (pin "VOUT") (pinfunction "OUT_VOUT") (pintype "output"))
    )
    (net (code "103") (name "unconnected-(JP3-Pad16)") (class "Default")
      (node (ref "JP3") (pin "16") (pinfunction "16_16") (pintype "passive"))
    )
    (net (code "104") (name "unconnected-(U$1-DEBUG_RX-Pad26)") (class "Default")
      (node (ref "U$1") (pin "26") (pinfunction "DEBUG_RX_26") (pintype "bidirectional"))
    )
    (net (code "105") (name "unconnected-(U$1-DEBUG_TX-Pad27)") (class "Default")
      (node (ref "U$1") (pin "27") (pinfunction "DEBUG_TX_27") (pintype "bidirectional"))
    )
    (net (code "106") (name "unconnected-(U$1-JTAG_EN-Pad21)") (class "Default")
      (node (ref "U$1") (pin "21") (pinfunction "JTAG_EN_21") (pintype "bidirectional"))
    )
    (net (code "107") (name "unconnected-(U$1-JTAG_RST-Pad9)") (class "Default")
      (node (ref "U$1") (pin "9") (pinfunction "JTAG_RST_9") (pintype "bidirectional"))
    )
    (net (code "108") (name "unconnected-(U$1-JTAG_TDI-Pad6)") (class "Default")
      (node (ref "U$1") (pin "6") (pinfunction "JTAG_TDI_6") (pintype "bidirectional"))
    )
    (net (code "109") (name "unconnected-(U$1-JTAG_TDO-Pad3)") (class "Default")
      (node (ref "U$1") (pin "3") (pinfunction "JTAG_TDO_3") (pintype "bidirectional"))
    )
    (net (code "110") (name "unconnected-(U$1-JTAG_TMS-Pad5)") (class "Default")
      (node (ref "U$1") (pin "5") (pinfunction "JTAG_TMS_5") (pintype "bidirectional"))
    )
    (net (code "111") (name "unconnected-(U$1-NC-Pad2)") (class "Default")
      (node (ref "U$1") (pin "2") (pinfunction "NC_2") (pintype "bidirectional"))
    )
    (net (code "112") (name "unconnected-(U$1-NC-Pad8)") (class "Default")
      (node (ref "U$1") (pin "8") (pinfunction "NC_8") (pintype "bidirectional"))
    )
    (net (code "113") (name "unconnected-(U$1-NC-Pad11)") (class "Default")
      (node (ref "U$1") (pin "11") (pinfunction "NC_11") (pintype "bidirectional"))
    )
    (net (code "114") (name "unconnected-(U$1-NC-Pad12)") (class "Default")
      (node (ref "U$1") (pin "12") (pinfunction "NC_12") (pintype "bidirectional"))
    )
    (net (code "115") (name "unconnected-(U$1-NC-Pad13)") (class "Default")
      (node (ref "U$1") (pin "13") (pinfunction "NC_13") (pintype "bidirectional"))
    )
    (net (code "116") (name "unconnected-(U$1-NC-Pad14)") (class "Default")
      (node (ref "U$1") (pin "14") (pinfunction "NC_14") (pintype "bidirectional"))
    )
    (net (code "117") (name "unconnected-(U$1-NC-Pad15)") (class "Default")
      (node (ref "U$1") (pin "15") (pinfunction "NC_15") (pintype "bidirectional"))
    )
    (net (code "118") (name "unconnected-(U$1-NC-Pad22)") (class "Default")
      (node (ref "U$1") (pin "22") (pinfunction "NC_22") (pintype "bidirectional"))
    )
    (net (code "119") (name "unconnected-(U$1-NC-Pad24)") (class "Default")
      (node (ref "U$1") (pin "24") (pinfunction "NC_24") (pintype "bidirectional"))
    )
    (net (code "120") (name "unconnected-(U$1-NC-Pad31)") (class "Default")
      (node (ref "U$1") (pin "31") (pinfunction "NC_31") (pintype "bidirectional"))
    )
    (net (code "121") (name "unconnected-(U$2-IRQ-Pad8)") (class "Default")
      (node (ref "U$2") (pin "8") (pinfunction "IRQ_8") (pintype "bidirectional"))
    )
    (net (code "122") (name "unconnected-(U$2-P9-Pad9)") (class "Default")
      (node (ref "U$2") (pin "9") (pinfunction "P9_9") (pintype "bidirectional"))
    )
  )
)
